# OnOnfre_dual_parafuso_ssr_rev3_4.net
KiCad netlist of a schematic drawn in EAGLE
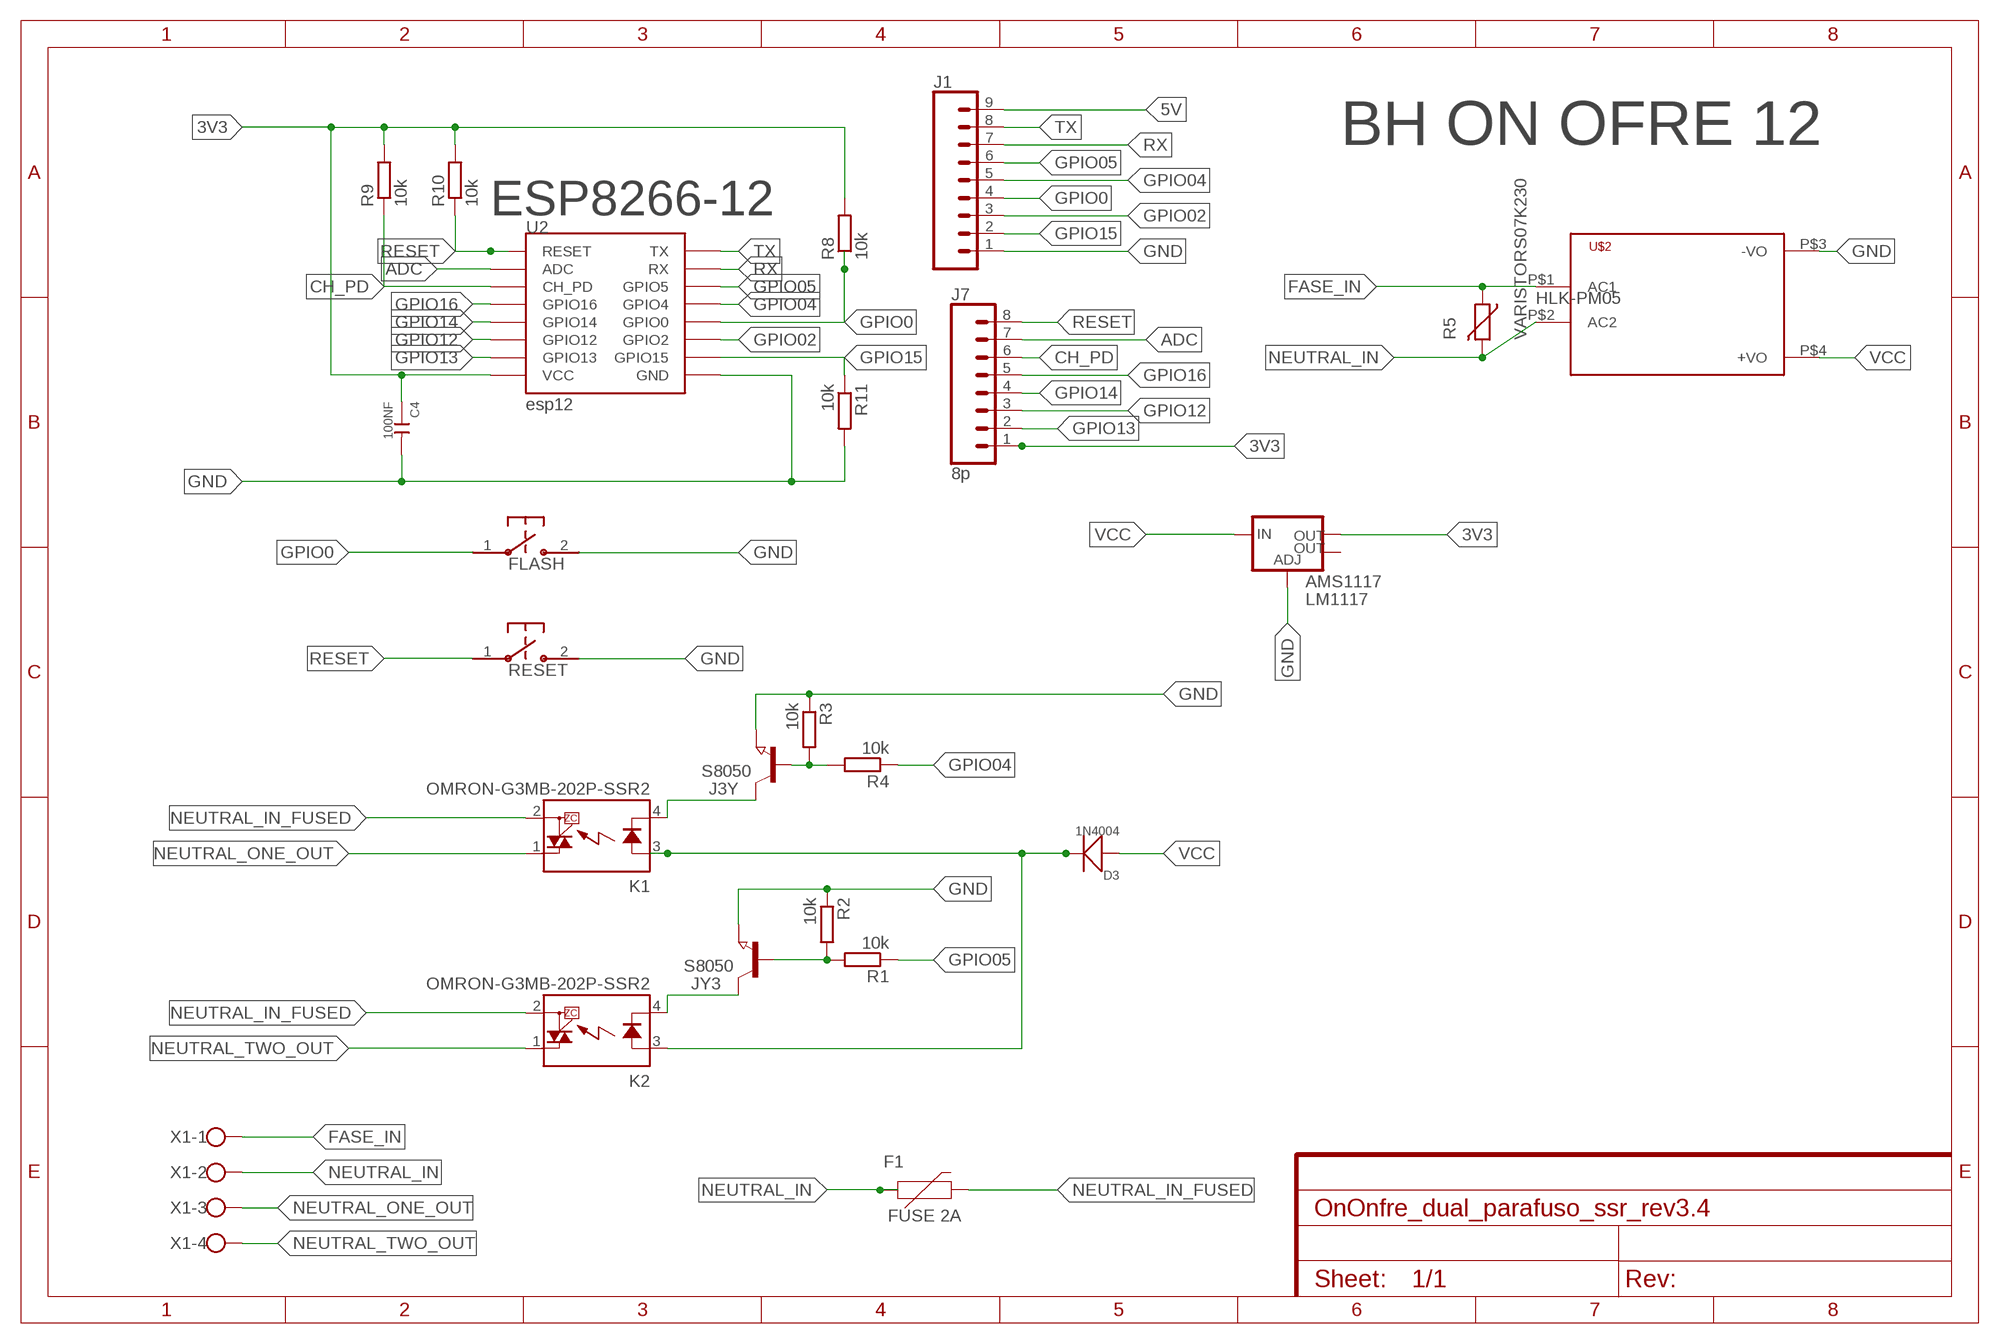
[diagram p0: schematic, sheet 1]

(export (version "E")
  (design (tool "Eeschema 10.0.6"))
  (components
    (comp (ref "AMS1117")
      (value "LM1117")
      (footprint "eagle-import:SOT223")
      (libsource (lib "eagle-import") (part "V_REG_LM1117SOT223"))
    )
    (comp (ref "C4")
      (value "100NF")
      (footprint "eagle-import:C1206")
      (fields (field (name "MPN") "CC1206KKX7RCBB102"))
      (libsource (lib "eagle-import") (part "CERAMIC-1NF-1KV-10%-X7R?(1206)"))
    )
    (comp (ref "D3")
      (value "1N4004")
      (footprint "eagle-import:DO-214AC")
      (fields (field (name "MPN") "1N4007"))
      (libsource (lib "eagle-import") (part "DIODE-GEN-PURPOSE-1KV-1A(DO-214AC)"))
    )
    (comp (ref "F1")
      (value "FUSE 2A")
      (footprint "eagle-import:PTH")
      (libsource (lib "eagle-import") (part "PPTC_PTH"))
    )
    (comp (ref "FLASH")
      (value "B3U-1000P-2P-SMD")
      (footprint "eagle-import:B3U-1000P")
      (fields (field (name "MANUFACTURER") "Omron") (field (name "MPN") "B3U-1000P"))
      (libsource (lib "eagle-import") (part "B3U-1000P"))
    )
    (comp (ref "J1")
      (value "CONN_09")
      (footprint "eagle-import:1X09")
      (libsource (lib "eagle-import") (part "CONN_09"))
    )
    (comp (ref "J3Y")
      (value "S8050")
      (footprint "eagle-import:SOT23")
      (libsource (lib "eagle-import") (part "NPN-TRANSISTOR_SOT23"))
    )
    (comp (ref "J7")
      (value "8p")
      (footprint "eagle-import:1X08")
      (libsource (lib "eagle-import") (part "CONN_08{dblquote}"))
    )
    (comp (ref "JY3")
      (value "S8050")
      (footprint "eagle-import:SOT23")
      (libsource (lib "eagle-import") (part "NPN-TRANSISTOR_SOT23"))
    )
    (comp (ref "K1")
      (value "OMRON-G3MB-202P-SSR2")
      (footprint "eagle-import:OMRON-G3MB-202P-SSR")
      (fields (field (name "MPN") "S202S02F"))
      (libsource (lib "eagle-import") (part "OMRON-G3MB-202P-SSR2"))
    )
    (comp (ref "K2")
      (value "OMRON-G3MB-202P-SSR2")
      (footprint "eagle-import:OMRON-G3MB-202P-SSR")
      (fields (field (name "MPN") "S202S02F"))
      (libsource (lib "eagle-import") (part "OMRON-G3MB-202P-SSR2"))
    )
    (comp (ref "R1")
      (value "10k")
      (footprint "eagle-import:R0603")
      (libsource (lib "eagle-import") (part "R-EU_R0603"))
    )
    (comp (ref "R2")
      (value "10k")
      (footprint "eagle-import:R0603")
      (libsource (lib "eagle-import") (part "R-EU_R0603"))
    )
    (comp (ref "R3")
      (value "10k")
      (footprint "eagle-import:R0603")
      (libsource (lib "eagle-import") (part "R-EU_R0603"))
    )
    (comp (ref "R4")
      (value "10k")
      (footprint "eagle-import:R0603")
      (libsource (lib "eagle-import") (part "R-EU_R0603"))
    )
    (comp (ref "R5")
      (value "VARISTORS07K230")
      (footprint "eagle-import:S07K230")
      (libsource (lib "eagle-import") (part "VARISTORS07K230"))
    )
    (comp (ref "R8")
      (value "10k")
      (footprint "eagle-import:R0603")
      (libsource (lib "eagle-import") (part "R-EU_R0603"))
    )
    (comp (ref "R9")
      (value "10k")
      (footprint "eagle-import:R0603")
      (libsource (lib "eagle-import") (part "R-EU_R0603"))
    )
    (comp (ref "R10")
      (value "10k")
      (footprint "eagle-import:R0603")
      (libsource (lib "eagle-import") (part "R-EU_R0603"))
    )
    (comp (ref "R11")
      (value "10k")
      (footprint "eagle-import:R0603")
      (libsource (lib "eagle-import") (part "R-EU_R0603"))
    )
    (comp (ref "RESET")
      (value "B3U-1000P-2P-SMD")
      (footprint "eagle-import:B3U-1000P")
      (fields (field (name "MANUFACTURER") "Omron") (field (name "MPN") "B3U-1000P"))
      (libsource (lib "eagle-import") (part "B3U-1000P"))
    )
    (comp (ref "U$2")
      (value "HKLPM01")
      (footprint "eagle-import:HKLPM01")
      (libsource (lib "eagle-import") (part "HKLPM01"))
    )
    (comp (ref "U2")
      (value "esp12")
      (footprint "eagle-import:ESP12-SMD")
      (libsource (lib "eagle-import") (part "ESP12SMD"))
    )
    (comp (ref "X1")
      (value "W237-4")
      (footprint "eagle-import:W237-4")
      (libsource (lib "eagle-import") (part "W237-4"))
    )
  )
  (nets
    (net (code "1") (name "3V3") (class "Default")
      (node (ref "AMS1117") (pin "2") (pinfunction "OUT_2") (pintype "output"))
      (node (ref "C4") (pin "1") (pinfunction "1_1") (pintype "passive"))
      (node (ref "J7") (pin "1") (pinfunction "1_1") (pintype "passive"))
      (node (ref "R10") (pin "2") (pinfunction "2_2") (pintype "passive"))
      (node (ref "R8") (pin "2") (pinfunction "2_2") (pintype "passive"))
      (node (ref "R9") (pin "2") (pinfunction "2_2") (pintype "passive"))
      (node (ref "U2") (pin "VCC") (pinfunction "VCC_VCC") (pintype "bidirectional"))
    )
    (net (code "2") (name "5V") (class "Default")
      (node (ref "D3") (pin "2") (pinfunction "-_2") (pintype "passive"))
      (node (ref "J1") (pin "9") (pinfunction "9_9") (pintype "passive"))
      (node (ref "K1") (pin "3") (pinfunction "A_3") (pintype "passive"))
      (node (ref "K2") (pin "3") (pinfunction "A_3") (pintype "passive"))
    )
    (net (code "3") (name "ADC") (class "Default")
      (node (ref "J7") (pin "7") (pinfunction "7_7") (pintype "passive"))
      (node (ref "U2") (pin "ADC") (pinfunction "ADC_ADC") (pintype "bidirectional"))
    )
    (net (code "4") (name "CH_PD") (class "Default")
      (node (ref "J7") (pin "6") (pinfunction "6_6") (pintype "passive"))
      (node (ref "R9") (pin "1") (pinfunction "1_1") (pintype "passive"))
      (node (ref "U2") (pin "CH_PD") (pinfunction "CH_PD_CH_PD") (pintype "bidirectional"))
    )
    (net (code "5") (name "FASE_IN") (class "Default")
      (node (ref "R5") (pin "1") (pinfunction "1_1") (pintype "passive"))
      (node (ref "U$2") (pin "P$1") (pinfunction "AC1_P$1") (pintype "bidirectional"))
      (node (ref "X1") (pin "1") (pinfunction "KL_1") (pintype "passive"))
    )
    (net (code "6") (name "GND") (class "Default")
      (node (ref "AMS1117") (pin "1") (pinfunction "ADJ_1") (pintype "input"))
      (node (ref "C4") (pin "2") (pinfunction "2_2") (pintype "passive"))
      (node (ref "FLASH") (pin "2") (pinfunction "P$2_2") (pintype "passive"))
      (node (ref "J1") (pin "1") (pinfunction "1_1") (pintype "passive"))
      (node (ref "J3Y") (pin "2") (pinfunction "E_2") (pintype "passive"))
      (node (ref "JY3") (pin "2") (pinfunction "E_2") (pintype "passive"))
      (node (ref "R11") (pin "2") (pinfunction "2_2") (pintype "passive"))
      (node (ref "R2") (pin "1") (pinfunction "1_1") (pintype "passive"))
      (node (ref "R3") (pin "1") (pinfunction "1_1") (pintype "passive"))
      (node (ref "RESET") (pin "2") (pinfunction "P$2_2") (pintype "passive"))
      (node (ref "U$2") (pin "P$3") (pinfunction "-VO_P$3") (pintype "bidirectional"))
      (node (ref "U2") (pin "GND") (pinfunction "GND_GND") (pintype "bidirectional"))
    )
    (net (code "7") (name "GPIO0") (class "Default")
      (node (ref "FLASH") (pin "1") (pinfunction "P$1_1") (pintype "passive"))
      (node (ref "J1") (pin "4") (pinfunction "4_4") (pintype "passive"))
      (node (ref "R8") (pin "1") (pinfunction "1_1") (pintype "passive"))
      (node (ref "U2") (pin "GPIO0") (pinfunction "GPIO0_GPIO0") (pintype "bidirectional"))
    )
    (net (code "8") (name "GPIO02") (class "Default")
      (node (ref "J1") (pin "3") (pinfunction "3_3") (pintype "passive"))
      (node (ref "U2") (pin "GPIO2") (pinfunction "GPIO2_GPIO2") (pintype "bidirectional"))
    )
    (net (code "9") (name "GPIO04") (class "Default")
      (node (ref "J1") (pin "5") (pinfunction "5_5") (pintype "passive"))
      (node (ref "R4") (pin "1") (pinfunction "1_1") (pintype "passive"))
      (node (ref "U2") (pin "GPIO4") (pinfunction "GPIO4_GPIO4") (pintype "bidirectional"))
    )
    (net (code "10") (name "GPIO05") (class "Default")
      (node (ref "J1") (pin "6") (pinfunction "6_6") (pintype "passive"))
      (node (ref "R1") (pin "1") (pinfunction "1_1") (pintype "passive"))
      (node (ref "U2") (pin "GPIO5") (pinfunction "GPIO5_GPIO5") (pintype "bidirectional"))
    )
    (net (code "11") (name "GPIO12") (class "Default")
      (node (ref "J7") (pin "3") (pinfunction "3_3") (pintype "passive"))
      (node (ref "U2") (pin "GPIO12") (pinfunction "GPIO12_GPIO12") (pintype "bidirectional"))
    )
    (net (code "12") (name "GPIO13") (class "Default")
      (node (ref "J7") (pin "2") (pinfunction "2_2") (pintype "passive"))
      (node (ref "U2") (pin "GPIO13") (pinfunction "GPIO13_GPIO13") (pintype "bidirectional"))
    )
    (net (code "13") (name "GPIO14") (class "Default")
      (node (ref "J7") (pin "4") (pinfunction "4_4") (pintype "passive"))
      (node (ref "U2") (pin "GPIO14") (pinfunction "GPIO14_GPIO14") (pintype "bidirectional"))
    )
    (net (code "14") (name "GPIO15") (class "Default")
      (node (ref "J1") (pin "2") (pinfunction "2_2") (pintype "passive"))
      (node (ref "R11") (pin "1") (pinfunction "1_1") (pintype "passive"))
      (node (ref "U2") (pin "GPIO15") (pinfunction "GPIO15_GPIO15") (pintype "bidirectional"))
    )
    (net (code "15") (name "GPIO16") (class "Default")
      (node (ref "J7") (pin "5") (pinfunction "5_5") (pintype "passive"))
      (node (ref "U2") (pin "GPIO16") (pinfunction "GPIO16_GPIO16") (pintype "bidirectional"))
    )
    (net (code "16") (name "NEUTRAL_IN") (class "Default")
      (node (ref "F1") (pin "P$1") (pinfunction "1_P$1") (pintype "bidirectional"))
      (node (ref "R5") (pin "2") (pinfunction "2_2") (pintype "passive"))
      (node (ref "U$2") (pin "P$2") (pinfunction "AC2_P$2") (pintype "bidirectional"))
      (node (ref "X1") (pin "2") (pinfunction "KL_2") (pintype "passive"))
    )
    (net (code "17") (name "NEUTRAL_IN_FUSED") (class "Default")
      (node (ref "F1") (pin "P$2") (pinfunction "2_P$2") (pintype "bidirectional"))
      (node (ref "K1") (pin "2") (pinfunction "DS2_2") (pintype "passive"))
      (node (ref "K2") (pin "2") (pinfunction "DS2_2") (pintype "passive"))
    )
    (net (code "18") (name "NEUTRAL_ONE_OUT") (class "Default")
      (node (ref "K1") (pin "1") (pinfunction "DS1_1") (pintype "passive"))
      (node (ref "X1") (pin "3") (pinfunction "KL_3") (pintype "passive"))
    )
    (net (code "19") (name "NEUTRAL_TWO_OUT") (class "Default")
      (node (ref "K2") (pin "1") (pinfunction "DS1_1") (pintype "passive"))
      (node (ref "X1") (pin "4") (pinfunction "KL_4") (pintype "passive"))
    )
    (net (code "20") (name "Net-(J3Y-B)") (class "Default")
      (node (ref "J3Y") (pin "1") (pinfunction "B_1") (pintype "passive"))
      (node (ref "R3") (pin "2") (pinfunction "2_2") (pintype "passive"))
      (node (ref "R4") (pin "2") (pinfunction "2_2") (pintype "passive"))
    )
    (net (code "21") (name "Net-(J3Y-C)") (class "Default")
      (node (ref "J3Y") (pin "3") (pinfunction "C_3") (pintype "passive"))
      (node (ref "K1") (pin "4") (pinfunction "K_4") (pintype "passive"))
    )
    (net (code "22") (name "Net-(JY3-B)") (class "Default")
      (node (ref "JY3") (pin "1") (pinfunction "B_1") (pintype "passive"))
      (node (ref "R1") (pin "2") (pinfunction "2_2") (pintype "passive"))
      (node (ref "R2") (pin "2") (pinfunction "2_2") (pintype "passive"))
    )
    (net (code "23") (name "Net-(JY3-C)") (class "Default")
      (node (ref "JY3") (pin "3") (pinfunction "C_3") (pintype "passive"))
      (node (ref "K2") (pin "4") (pinfunction "K_4") (pintype "passive"))
    )
    (net (code "24") (name "RESET") (class "Default")
      (node (ref "J7") (pin "8") (pinfunction "8_8") (pintype "passive"))
      (node (ref "R10") (pin "1") (pinfunction "1_1") (pintype "passive"))
      (node (ref "RESET") (pin "1") (pinfunction "P$1_1") (pintype "passive"))
      (node (ref "U2") (pin "RESET") (pinfunction "RESET_RESET") (pintype "bidirectional"))
    )
    (net (code "25") (name "RX") (class "Default")
      (node (ref "J1") (pin "7") (pinfunction "7_7") (pintype "passive"))
      (node (ref "U2") (pin "RXD0") (pinfunction "RX_RXD0") (pintype "bidirectional"))
    )
    (net (code "26") (name "TX") (class "Default")
      (node (ref "J1") (pin "8") (pinfunction "8_8") (pintype "passive"))
      (node (ref "U2") (pin "TXD0") (pinfunction "TX_TXD0") (pintype "bidirectional"))
    )
    (net (code "27") (name "VCC") (class "Default")
      (node (ref "AMS1117") (pin "3") (pinfunction "IN_3") (pintype "input"))
      (node (ref "D3") (pin "1") (pinfunction "+_1") (pintype "passive"))
      (node (ref "U$2") (pin "P$4") (pinfunction "+VO_P$4") (pintype "bidirectional"))
    )
    (net (code "28") (name "unconnected-(AMS1117-OUT-Pad4)") (class "Default")
      (node (ref "AMS1117") (pin "4") (pinfunction "OUT_4") (pintype "output"))
    )
  )
)
